# sch_USB3_0.net
KiCad netlist of a schematic drawn in Altium Designer
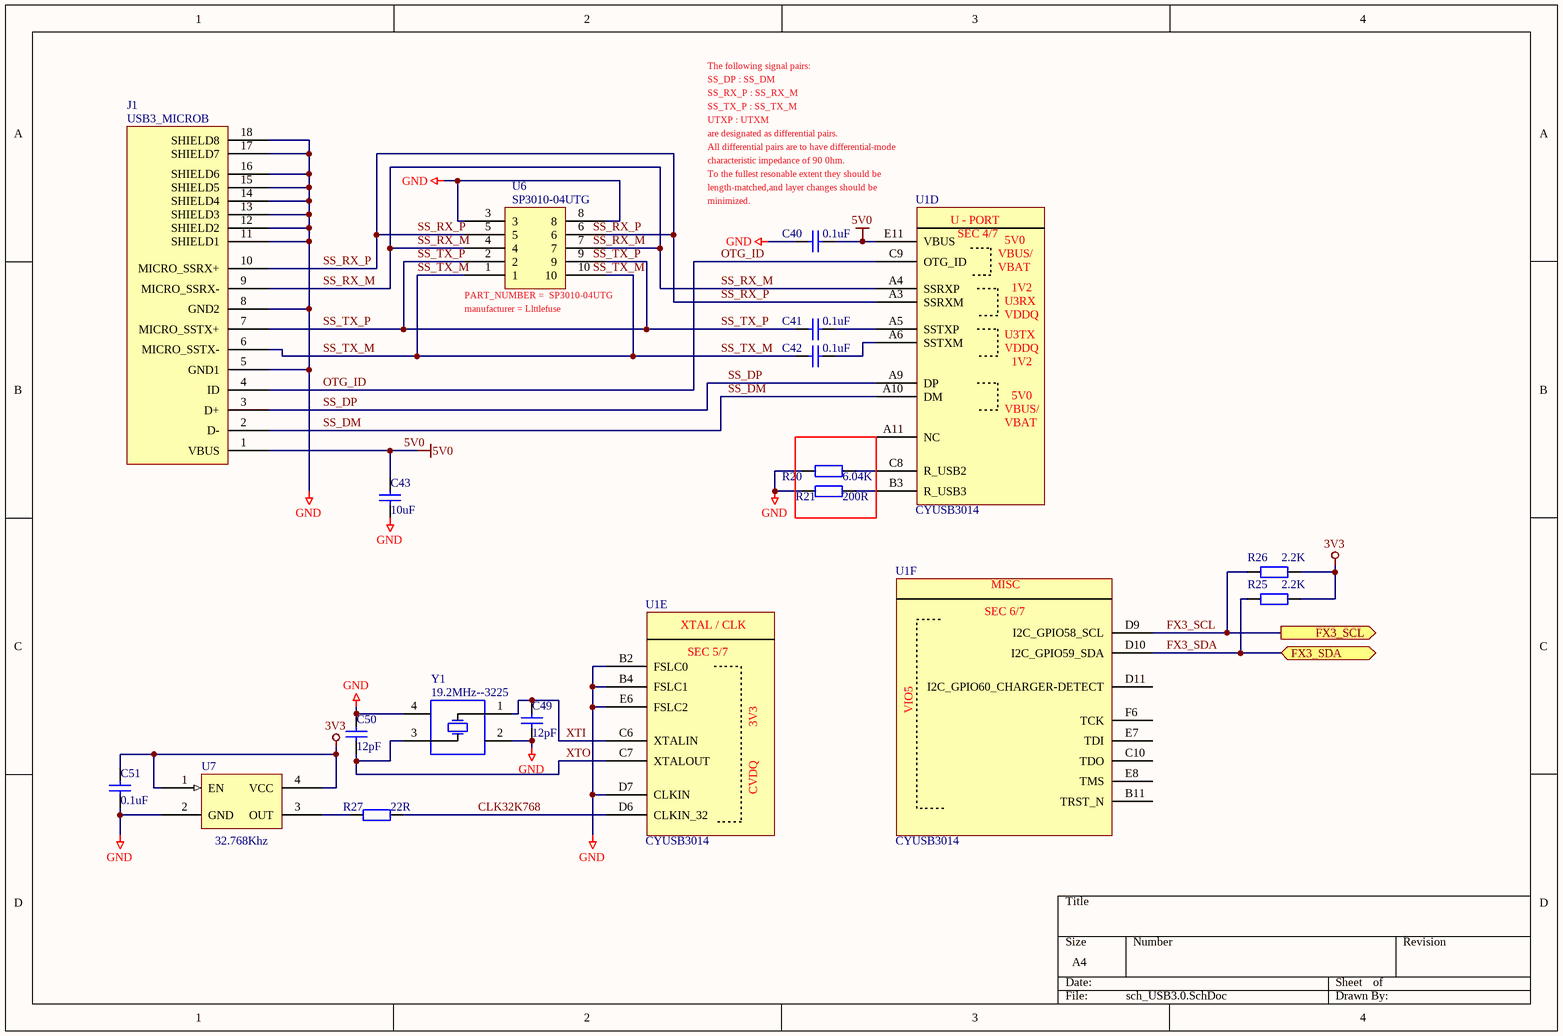
[diagram p0: sch_USB3.0.SchDoc]

(export (version "E")
  (design (tool "Eeschema 10.0.6"))
  (components
    (comp (ref "C40")
      (value "0.1uF")
      (footprint "0402C")
      (description "Capacitor")
      (fields (field (name "PUBLISHER") "Altium Limited"))
      (libsource (lib "Miscellaneous Devices") (part "Cap"))
    )
    (comp (ref "C41")
      (value "0.1uF")
      (footprint "0402C")
      (description "Capacitor")
      (fields (field (name "PUBLISHER") "Altium Limited"))
      (libsource (lib "Miscellaneous Devices") (part "Cap"))
    )
    (comp (ref "C42")
      (value "0.1uF")
      (footprint "0402C")
      (description "Capacitor")
      (fields (field (name "PUBLISHER") "Altium Limited"))
      (libsource (lib "Miscellaneous Devices") (part "Cap"))
    )
    (comp (ref "C43")
      (value "10uF")
      (footprint "0805C")
      (description "Capacitor")
      (fields (field (name "PUBLISHER") "Altium Limited"))
      (libsource (lib "Miscellaneous Devices") (part "Cap"))
    )
    (comp (ref "C49")
      (value "12pF")
      (footprint "0402C")
      (description "Capacitor")
      (fields (field (name "PUBLISHER") "Altium Limited"))
      (libsource (lib "Miscellaneous Devices") (part "Cap"))
    )
    (comp (ref "C50")
      (value "12pF")
      (footprint "0402C")
      (description "Capacitor")
      (fields (field (name "PUBLISHER") "Altium Limited"))
      (libsource (lib "Miscellaneous Devices") (part "Cap"))
    )
    (comp (ref "C51")
      (value "0.1uF")
      (footprint "0402C")
      (description "Capacitor")
      (fields (field (name "PUBLISHER") "Altium Limited"))
      (libsource (lib "Miscellaneous Devices") (part "Cap"))
    )
    (comp (ref "J1")
      (value "USB3_MICROB")
      (footprint "USB3_BA_P65L130W51H28")
      (libsource (lib "SZG") (part "USB3_MICROB"))
    )
    (comp (ref "R20")
      (value "6.04K")
      (footprint "0402R")
      (description "Resistor")
      (fields (field (name "PUBLISHER") "Altium Limited"))
      (libsource (lib "SZG") (part "Resistor"))
    )
    (comp (ref "R21")
      (value "200R")
      (footprint "0402R")
      (description "Resistor")
      (fields (field (name "PUBLISHER") "Altium Limited"))
      (libsource (lib "SZG") (part "Resistor"))
    )
    (comp (ref "R25")
      (value "2.2K")
      (footprint "0402R")
      (description "Resistor")
      (fields (field (name "PUBLISHER") "Altium Limited"))
      (libsource (lib "SZG") (part "Resistor"))
    )
    (comp (ref "R26")
      (value "2.2K")
      (footprint "0402R")
      (description "Resistor")
      (fields (field (name "PUBLISHER") "Altium Limited"))
      (libsource (lib "SZG") (part "Resistor"))
    )
    (comp (ref "R27")
      (value "22R")
      (footprint "0402R")
      (description "Resistor")
      (fields (field (name "PUBLISHER") "Altium Limited"))
      (libsource (lib "SZG") (part "Resistor"))
    )
    (comp (ref "U1")
      (value "CYUSB3014")
      (footprint "FBGA121_P80L100W100H11")
      (libsource (lib "TXW") (part "CYUSB3014"))
    )
    (comp (ref "U6")
      (value "SP3010-04UTG")
      (footprint "UDFN10_SON_P50L25W10H55")
      (libsource (lib "SZG") (part "SP3010-04UTG"))
    )
    (comp (ref "U7")
      (value "XTAL-3225")
      (footprint "XTAL_3225")
      (libsource (lib "常用晶振器件图SCH") (part "XTAL."))
    )
    (comp (ref "Y1")
      (value "19.2MHz--3225")
      (footprint "XTAL_3225")
      (description "Crystal Oscillator")
      (libsource (lib "常用晶振器件图SCH") (part "XTAL"))
    )
  )
  (nets
    (net (code "1") (name "/CLK32K768") (class "Default")
      (node (ref "R27") (pin "1") (pinfunction "1_1") (pintype "passive"))
      (node (ref "U1") (pin "D6") (pinfunction "CLKIN_32_D6") (pintype "passive"))
    )
    (net (code "2") (name "/FX3_SCL") (class "Default")
      (node (ref "R26") (pin "2") (pinfunction "2_2") (pintype "passive"))
      (node (ref "U1") (pin "D9") (pinfunction "I2C_GPIO58_SCL_D9") (pintype "passive"))
    )
    (net (code "3") (name "/FX3_SDA") (class "Default")
      (node (ref "R25") (pin "2") (pinfunction "2_2") (pintype "passive"))
      (node (ref "U1") (pin "D10") (pinfunction "I2C_GPIO59_SDA_D10") (pintype "passive"))
    )
    (net (code "4") (name "/OTG_ID") (class "Default")
      (node (ref "J1") (pin "4") (pinfunction "ID_4") (pintype "power_in"))
      (node (ref "U1") (pin "C9") (pinfunction "OTG_ID_C9") (pintype "power_in"))
    )
    (net (code "5") (name "/SS_DM") (class "Default")
      (node (ref "J1") (pin "2") (pinfunction "D-_2") (pintype "power_in"))
      (node (ref "U1") (pin "A10") (pinfunction "DM_A10") (pintype "power_in"))
    )
    (net (code "6") (name "/SS_DP") (class "Default")
      (node (ref "J1") (pin "3") (pinfunction "D+_3") (pintype "power_in"))
      (node (ref "U1") (pin "A9") (pinfunction "DP_A9") (pintype "power_in"))
    )
    (net (code "7") (name "/SS_RX_M") (class "Default")
      (node (ref "J1") (pin "9") (pinfunction "MICRO_SSRX-_9") (pintype "power_in"))
      (node (ref "U1") (pin "A4") (pinfunction "SSRXP_A4") (pintype "power_in"))
      (node (ref "U6") (pin "4") (pinfunction "4_4") (pintype "passive"))
      (node (ref "U6") (pin "7") (pinfunction "7_7") (pintype "passive"))
    )
    (net (code "8") (name "/SS_RX_P") (class "Default")
      (node (ref "J1") (pin "10") (pinfunction "MICRO_SSRX+_10") (pintype "power_in"))
      (node (ref "U1") (pin "A3") (pinfunction "SSRXM_A3") (pintype "power_in"))
      (node (ref "U6") (pin "5") (pinfunction "5_5") (pintype "passive"))
      (node (ref "U6") (pin "6") (pinfunction "6_6") (pintype "passive"))
    )
    (net (code "9") (name "/SS_TX_M") (class "Default")
      (node (ref "C42") (pin "2") (pinfunction "2_2") (pintype "passive"))
      (node (ref "J1") (pin "6") (pinfunction "MICRO_SSTX-_6") (pintype "power_in"))
      (node (ref "U6") (pin "1") (pinfunction "1_1") (pintype "passive"))
      (node (ref "U6") (pin "10") (pinfunction "10_10") (pintype "passive"))
    )
    (net (code "10") (name "/SS_TX_P") (class "Default")
      (node (ref "C41") (pin "2") (pinfunction "2_2") (pintype "passive"))
      (node (ref "J1") (pin "7") (pinfunction "MICRO_SSTX+_7") (pintype "power_in"))
      (node (ref "U6") (pin "2") (pinfunction "2_2") (pintype "passive"))
      (node (ref "U6") (pin "9") (pinfunction "9_9") (pintype "passive"))
    )
    (net (code "11") (name "/XTI") (class "Default")
      (node (ref "C49") (pin "2") (pinfunction "2_2") (pintype "passive"))
      (node (ref "U1") (pin "C6") (pinfunction "XTALIN_C6") (pintype "passive"))
      (node (ref "Y1") (pin "1") (pinfunction "1_1") (pintype "passive"))
    )
    (net (code "12") (name "/XTO") (class "Default")
      (node (ref "C50") (pin "1") (pinfunction "1_1") (pintype "passive"))
      (node (ref "U1") (pin "C7") (pinfunction "XTALOUT_C7") (pintype "passive"))
      (node (ref "Y1") (pin "3") (pinfunction "3_3") (pintype "passive"))
    )
    (net (code "13") (name "3V3") (class "Default")
      (node (ref "C51") (pin "2") (pinfunction "2_2") (pintype "passive"))
      (node (ref "R25") (pin "1") (pinfunction "1_1") (pintype "passive"))
      (node (ref "R26") (pin "1") (pinfunction "1_1") (pintype "passive"))
      (node (ref "U7") (pin "1") (pinfunction "EN_1") (pintype "input"))
      (node (ref "U7") (pin "4") (pinfunction "VCC_4") (pintype "passive"))
    )
    (net (code "14") (name "5V0") (class "Default")
      (node (ref "C40") (pin "1") (pinfunction "1_1") (pintype "passive"))
      (node (ref "C43") (pin "2") (pinfunction "2_2") (pintype "passive"))
      (node (ref "J1") (pin "1") (pinfunction "VBUS_1") (pintype "power_in"))
      (node (ref "U1") (pin "E11") (pinfunction "VBUS_E11") (pintype "power_in"))
    )
    (net (code "15") (name "GND") (class "Default")
      (node (ref "C40") (pin "2") (pinfunction "2_2") (pintype "passive"))
      (node (ref "C43") (pin "1") (pinfunction "1_1") (pintype "passive"))
      (node (ref "C49") (pin "1") (pinfunction "1_1") (pintype "passive"))
      (node (ref "C50") (pin "2") (pinfunction "2_2") (pintype "passive"))
      (node (ref "C51") (pin "1") (pinfunction "1_1") (pintype "passive"))
      (node (ref "J1") (pin "11") (pinfunction "SHIELD1_11") (pintype "power_in"))
      (node (ref "J1") (pin "12") (pinfunction "SHIELD2_12") (pintype "power_in"))
      (node (ref "J1") (pin "13") (pinfunction "SHIELD3_13") (pintype "power_in"))
      (node (ref "J1") (pin "14") (pinfunction "SHIELD4_14") (pintype "power_in"))
      (node (ref "J1") (pin "15") (pinfunction "SHIELD5_15") (pintype "power_in"))
      (node (ref "J1") (pin "16") (pinfunction "SHIELD6_16") (pintype "power_in"))
      (node (ref "J1") (pin "17") (pinfunction "SHIELD7_17") (pintype "power_in"))
      (node (ref "J1") (pin "18") (pinfunction "SHIELD8_18") (pintype "power_in"))
      (node (ref "J1") (pin "5") (pinfunction "GND1_5") (pintype "power_in"))
      (node (ref "J1") (pin "8") (pinfunction "GND2_8") (pintype "power_in"))
      (node (ref "R20") (pin "2") (pinfunction "2_2") (pintype "passive"))
      (node (ref "R21") (pin "2") (pinfunction "2_2") (pintype "passive"))
      (node (ref "U1") (pin "B2") (pinfunction "FSLC0_B2") (pintype "passive"))
      (node (ref "U1") (pin "B4") (pinfunction "FSLC1_B4") (pintype "passive"))
      (node (ref "U1") (pin "D7") (pinfunction "CLKIN_D7") (pintype "passive"))
      (node (ref "U1") (pin "E6") (pinfunction "FSLC2_E6") (pintype "passive"))
      (node (ref "U6") (pin "3") (pinfunction "3_3") (pintype "passive"))
      (node (ref "U6") (pin "8") (pinfunction "8_8") (pintype "passive"))
      (node (ref "U7") (pin "2") (pinfunction "GND_2") (pintype "passive"))
      (node (ref "Y1") (pin "2") (pinfunction "2_2") (pintype "passive"))
      (node (ref "Y1") (pin "4") (pinfunction "4_4") (pintype "passive"))
    )
    (net (code "16") (name "Net-(U1D-R_USB2)") (class "Default")
      (node (ref "R20") (pin "1") (pinfunction "1_1") (pintype "passive"))
      (node (ref "U1") (pin "C8") (pinfunction "R_USB2_C8") (pintype "power_in"))
    )
    (net (code "17") (name "Net-(U1D-R_USB3)") (class "Default")
      (node (ref "R21") (pin "1") (pinfunction "1_1") (pintype "passive"))
      (node (ref "U1") (pin "B3") (pinfunction "R_USB3_B3") (pintype "power_in"))
    )
    (net (code "18") (name "Net-(U1D-SSTXM)") (class "Default")
      (node (ref "C42") (pin "1") (pinfunction "1_1") (pintype "passive"))
      (node (ref "U1") (pin "A6") (pinfunction "SSTXM_A6") (pintype "power_in"))
    )
    (net (code "19") (name "Net-(U1D-SSTXP)") (class "Default")
      (node (ref "C41") (pin "1") (pinfunction "1_1") (pintype "passive"))
      (node (ref "U1") (pin "A5") (pinfunction "SSTXP_A5") (pintype "power_in"))
    )
    (net (code "20") (name "Net-(U7-OUT)") (class "Default")
      (node (ref "R27") (pin "2") (pinfunction "2_2") (pintype "passive"))
      (node (ref "U7") (pin "3") (pinfunction "OUT_3") (pintype "passive"))
    )
    (net (code "21") (name "unconnected-(U1D-NC-PadA11)") (class "Default")
      (node (ref "U1") (pin "A11") (pinfunction "NC_A11") (pintype "power_in"))
    )
    (net (code "22") (name "unconnected-(U1F-I2C_GPIO60_CHARGER-DETECT-PadD11)") (class "Default")
      (node (ref "U1") (pin "D11") (pinfunction "I2C_GPIO60_CHARGER-DETECT_D11") (pintype "passive"))
    )
    (net (code "23") (name "unconnected-(U1F-TCK-PadF6)") (class "Default")
      (node (ref "U1") (pin "F6") (pinfunction "TCK_F6") (pintype "passive"))
    )
    (net (code "24") (name "unconnected-(U1F-TDI-PadE7)") (class "Default")
      (node (ref "U1") (pin "E7") (pinfunction "TDI_E7") (pintype "passive"))
    )
    (net (code "25") (name "unconnected-(U1F-TDO-PadC10)") (class "Default")
      (node (ref "U1") (pin "C10") (pinfunction "TDO_C10") (pintype "passive"))
    )
    (net (code "26") (name "unconnected-(U1F-TMS-PadE8)") (class "Default")
      (node (ref "U1") (pin "E8") (pinfunction "TMS_E8") (pintype "passive"))
    )
    (net (code "27") (name "unconnected-(U1F-TRST_N-PadB11)") (class "Default")
      (node (ref "U1") (pin "B11") (pinfunction "TRST_N_B11") (pintype "passive"))
    )
  )
)
